# SCH.net
KiCad netlist of a schematic drawn in EasyEDA
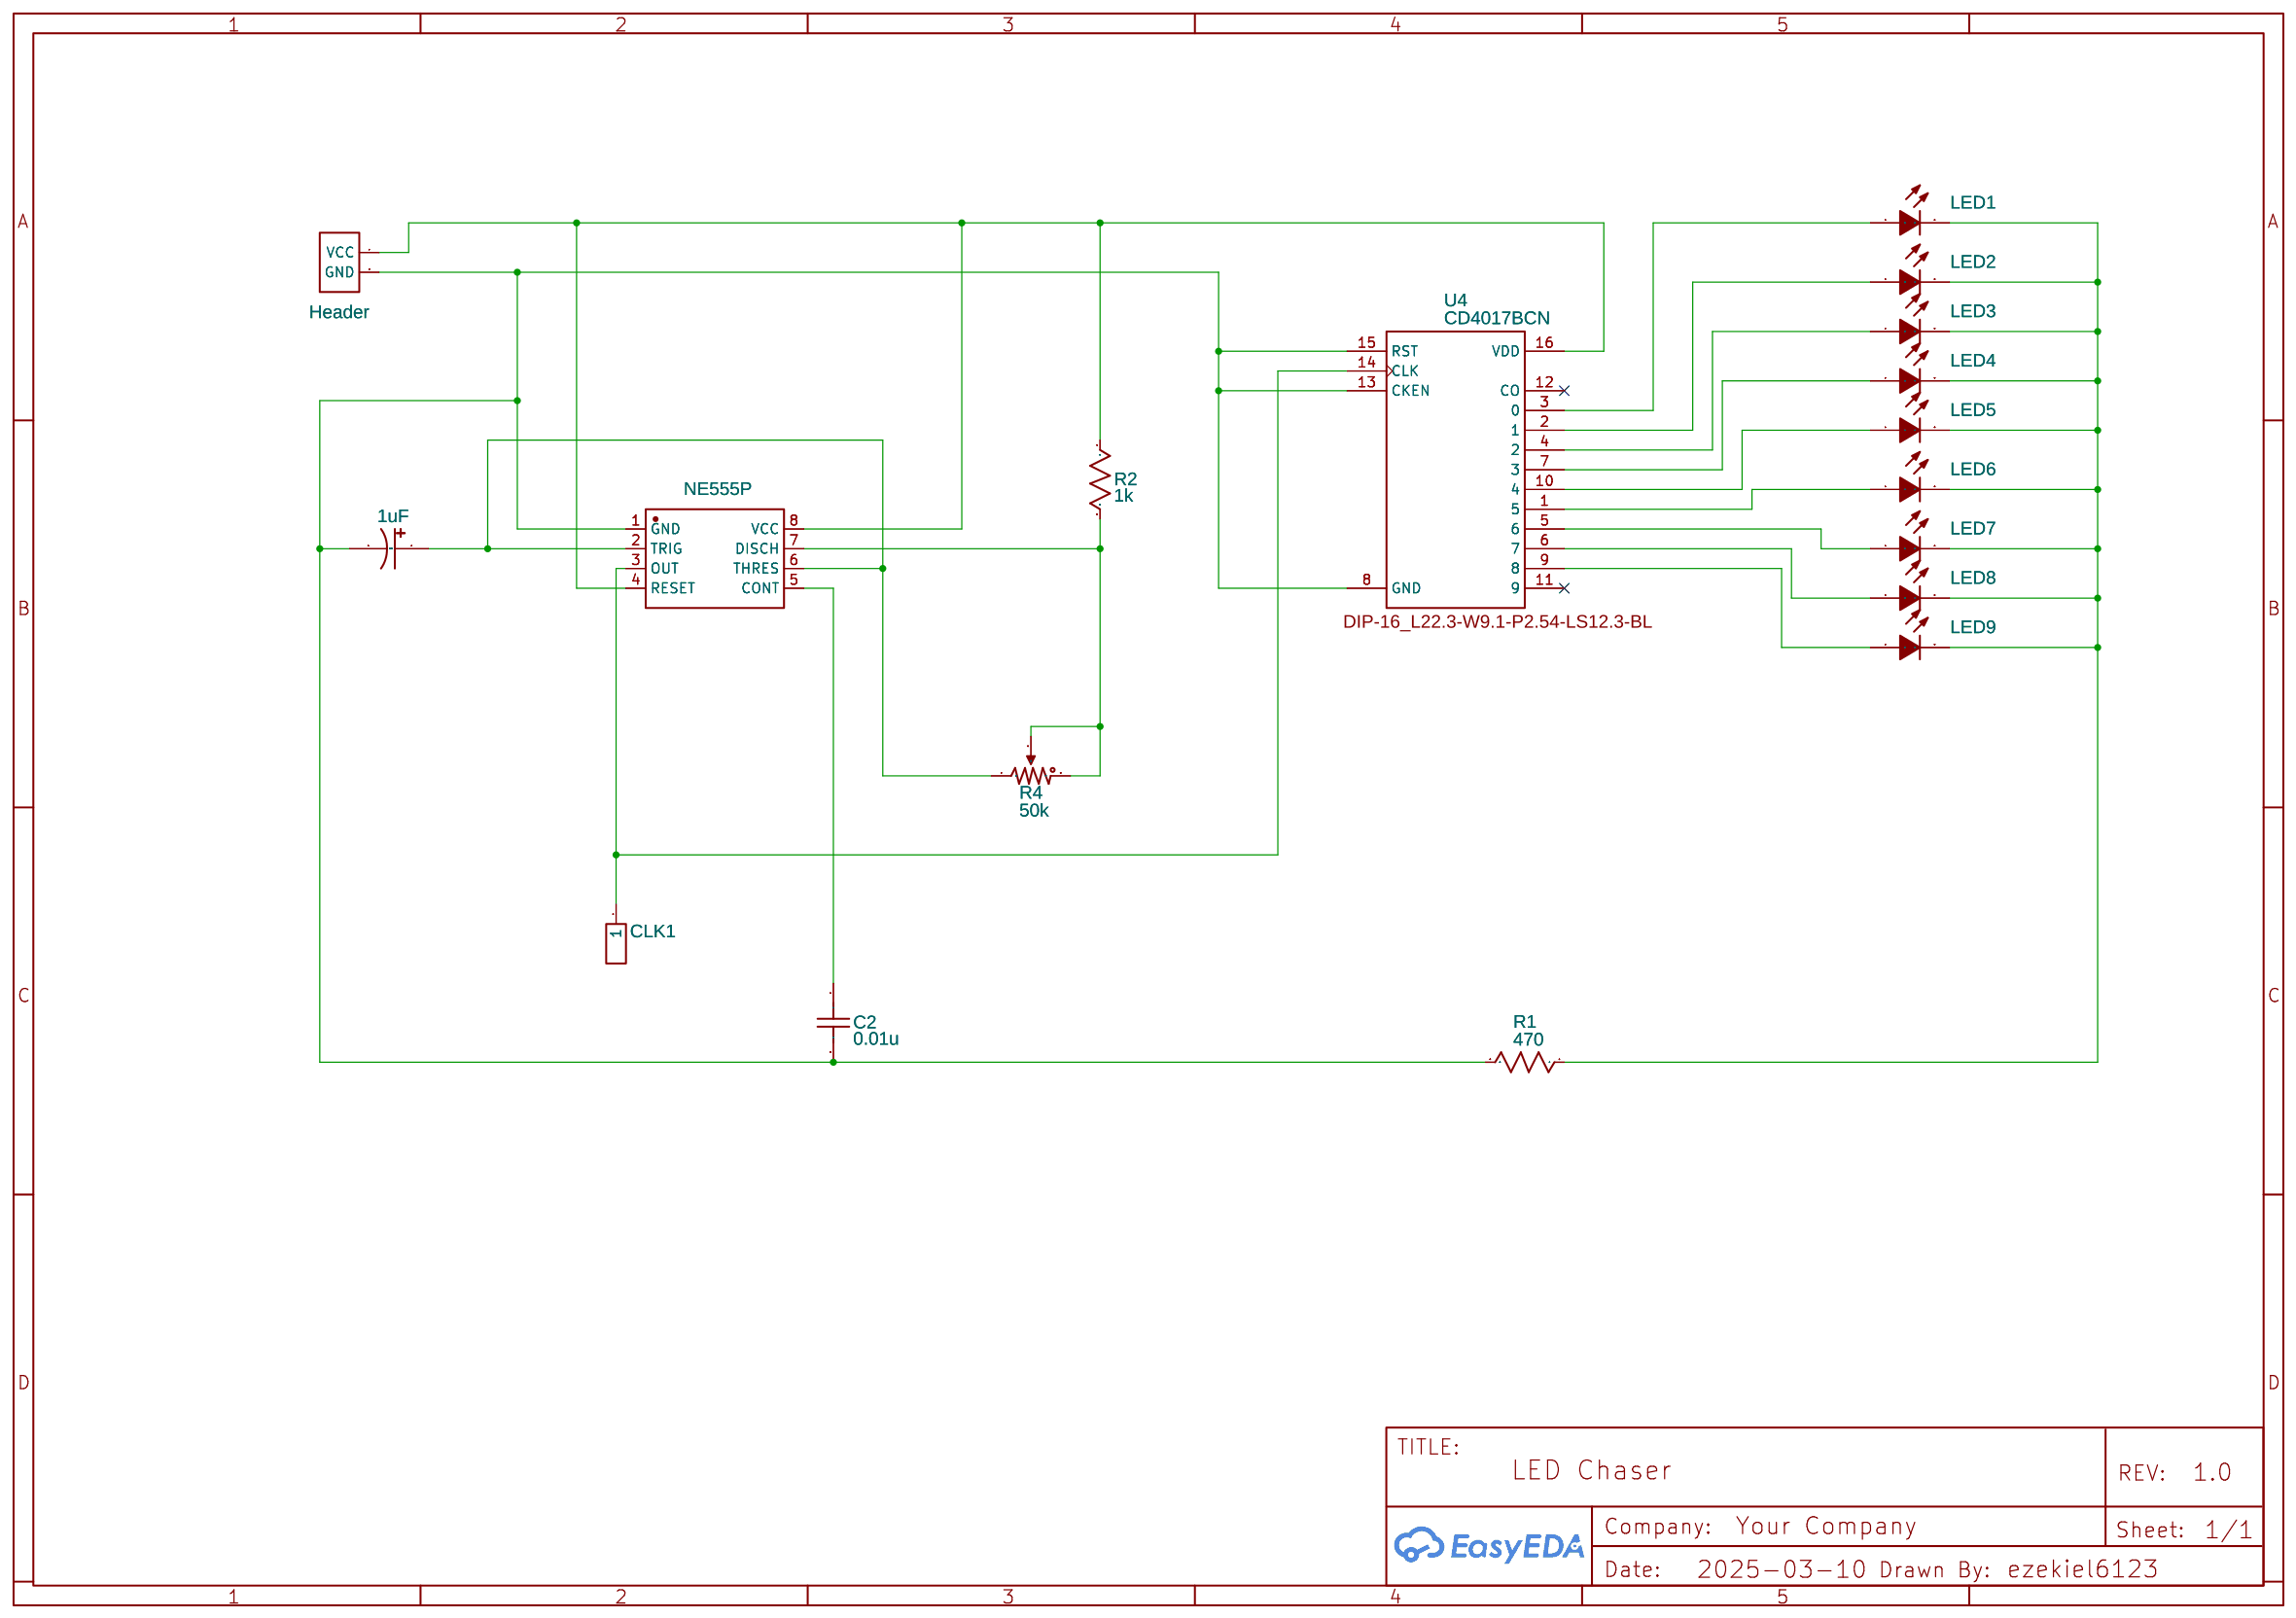
[diagram p0: schematic sheet]

(export (version "E")
  (design (tool "Eeschema 10.0.6"))
  (components
    (comp (ref "C1")
      (value "1uF")
      (fields (field (name "Manufacturer Part") "UVZ1H010MDD") (field (name "Manufacturer") "Nichicon(尼吉康)"))
      (libsource (lib "") (part "UVZ1H010MDD"))
    )
    (comp (ref "C2") (value "0.01u") (libsource (lib "") (part "C_0603_US")))
    (comp (ref "CLK1")
      (value "C81276")
      (fields
        (field (name "Manufacturer Part") "2.54-1*1P针")
        (field (name "Manufacturer") "BOOMELE(Boom Precision Elec)")
      )
      (libsource (lib "") (part "Header-Male-2.54_1x1"))
    )
    (comp (ref "H1") (value "Header") (libsource (lib "") (part "HEADER-FEMALE-2.54_1X2")))
    (comp (ref "LED1") (value "LED_5MM") (libsource (lib "") (part "LED_5MM")))
    (comp (ref "LED2") (value "LED_5MM") (libsource (lib "") (part "LED_5MM")))
    (comp (ref "LED3") (value "LED_5MM") (libsource (lib "") (part "LED_5MM")))
    (comp (ref "LED4") (value "LED_5MM") (libsource (lib "") (part "LED_5MM")))
    (comp (ref "LED5") (value "LED_5MM") (libsource (lib "") (part "LED_5MM")))
    (comp (ref "LED6") (value "LED_5MM") (libsource (lib "") (part "LED_5MM")))
    (comp (ref "LED7") (value "LED_5MM") (libsource (lib "") (part "LED_5MM")))
    (comp (ref "LED8") (value "LED_5MM") (libsource (lib "") (part "LED_5MM")))
    (comp (ref "LED9") (value "LED_5MM") (libsource (lib "") (part "LED_5MM")))
    (comp (ref "R1")
      (value "470")
      (fields (field (name "Manufacturer Part") "?"))
      (libsource (lib "") (part "Resistor"))
    )
    (comp (ref "R2")
      (value "1k")
      (fields (field (name "Manufacturer Part") "?"))
      (libsource (lib "") (part "Resistor_1"))
    )
    (comp (ref "R4")
      (value "50k")
      (fields (field (name "Manufacturer Part") "?"))
      (libsource (lib "") (part "Potentiometer"))
    )
    (comp (ref "U2")
      (value "NE555P")
      (fields (field (name "Manufacturer") "TI(德州仪器)"))
      (libsource (lib "") (part "NE555P"))
    )
    (comp (ref "U4") (value "CD4017BCN") (libsource (lib "") (part "CD4017BCN")))
  )
  (nets
    (net (code "1") (name "Net-(H1-GND)") (class "Default")
      (node (ref "C1") (pin "2") (pinfunction "2_2") (pintype "unspecified"))
      (node (ref "C2") (pin "2") (pinfunction "2_2") (pintype "unspecified"))
      (node (ref "H1") (pin "2") (pinfunction "GND_2") (pintype "unspecified"))
      (node (ref "R1") (pin "2") (pinfunction "2_2") (pintype "unspecified"))
      (node (ref "U2") (pin "1") (pinfunction "GND_1") (pintype "unspecified"))
      (node (ref "U4") (pin "13") (pinfunction "CKEN_13") (pintype "unspecified"))
      (node (ref "U4") (pin "15") (pinfunction "RST_15") (pintype "unspecified"))
      (node (ref "U4") (pin "8") (pinfunction "GND_8") (pintype "passive"))
    )
    (net (code "2") (name "Net-(H1-VCC)") (class "Default")
      (node (ref "H1") (pin "1") (pinfunction "VCC_1") (pintype "unspecified"))
      (node (ref "R2") (pin "1") (pinfunction "1_1") (pintype "unspecified"))
      (node (ref "U2") (pin "4") (pinfunction "RESET_4") (pintype "unspecified"))
      (node (ref "U2") (pin "8") (pinfunction "VCC_8") (pintype "unspecified"))
      (node (ref "U4") (pin "16") (pinfunction "VDD_16") (pintype "passive"))
    )
    (net (code "3") (name "Net-(LED1-A)") (class "Default")
      (node (ref "LED1") (pin "1") (pinfunction "A_1") (pintype "input"))
      (node (ref "U4") (pin "3") (pinfunction "0_3") (pintype "output"))
    )
    (net (code "4") (name "Net-(LED1-K)") (class "Default")
      (node (ref "LED1") (pin "2") (pinfunction "K_2") (pintype "input"))
      (node (ref "LED2") (pin "2") (pinfunction "K_2") (pintype "input"))
      (node (ref "LED3") (pin "2") (pinfunction "K_2") (pintype "input"))
      (node (ref "LED4") (pin "2") (pinfunction "K_2") (pintype "input"))
      (node (ref "LED5") (pin "2") (pinfunction "K_2") (pintype "input"))
      (node (ref "LED6") (pin "2") (pinfunction "K_2") (pintype "input"))
      (node (ref "LED7") (pin "2") (pinfunction "K_2") (pintype "input"))
      (node (ref "LED8") (pin "2") (pinfunction "K_2") (pintype "input"))
      (node (ref "LED9") (pin "2") (pinfunction "K_2") (pintype "input"))
      (node (ref "R1") (pin "1") (pinfunction "1_1") (pintype "unspecified"))
    )
    (net (code "5") (name "Net-(LED2-A)") (class "Default")
      (node (ref "LED2") (pin "1") (pinfunction "A_1") (pintype "input"))
      (node (ref "U4") (pin "2") (pinfunction "1_2") (pintype "output"))
    )
    (net (code "6") (name "Net-(LED3-A)") (class "Default")
      (node (ref "LED3") (pin "1") (pinfunction "A_1") (pintype "input"))
      (node (ref "U4") (pin "4") (pinfunction "2_4") (pintype "output"))
    )
    (net (code "7") (name "Net-(LED4-A)") (class "Default")
      (node (ref "LED4") (pin "1") (pinfunction "A_1") (pintype "input"))
      (node (ref "U4") (pin "7") (pinfunction "3_7") (pintype "output"))
    )
    (net (code "8") (name "Net-(LED5-A)") (class "Default")
      (node (ref "LED5") (pin "1") (pinfunction "A_1") (pintype "input"))
      (node (ref "U4") (pin "10") (pinfunction "4_10") (pintype "output"))
    )
    (net (code "9") (name "Net-(LED6-A)") (class "Default")
      (node (ref "LED6") (pin "1") (pinfunction "A_1") (pintype "input"))
      (node (ref "U4") (pin "1") (pinfunction "5_1") (pintype "output"))
    )
    (net (code "10") (name "Net-(LED7-A)") (class "Default")
      (node (ref "LED7") (pin "1") (pinfunction "A_1") (pintype "input"))
      (node (ref "U4") (pin "5") (pinfunction "6_5") (pintype "output"))
    )
    (net (code "11") (name "Net-(LED8-A)") (class "Default")
      (node (ref "LED8") (pin "1") (pinfunction "A_1") (pintype "input"))
      (node (ref "U4") (pin "6") (pinfunction "7_6") (pintype "output"))
    )
    (net (code "12") (name "Net-(LED9-A)") (class "Default")
      (node (ref "LED9") (pin "1") (pinfunction "A_1") (pintype "input"))
      (node (ref "U4") (pin "9") (pinfunction "8_9") (pintype "output"))
    )
    (net (code "13") (name "Net-(R4-2)") (class "Default")
      (node (ref "R2") (pin "2") (pinfunction "2_2") (pintype "unspecified"))
      (node (ref "R4") (pin "2") (pinfunction "3_2") (pintype "unspecified"))
      (node (ref "R4") (pin "3") (pinfunction "2_3") (pintype "unspecified"))
      (node (ref "U2") (pin "7") (pinfunction "DISCH_7") (pintype "unspecified"))
    )
    (net (code "14") (name "Net-(U2-CONT)") (class "Default")
      (node (ref "C2") (pin "1") (pinfunction "1_1") (pintype "unspecified"))
      (node (ref "U2") (pin "5") (pinfunction "CONT_5") (pintype "unspecified"))
    )
    (net (code "15") (name "Net-(U2-OUT)") (class "Default")
      (node (ref "CLK1") (pin "1") (pinfunction "1_1") (pintype "unspecified"))
      (node (ref "U2") (pin "3") (pinfunction "OUT_3") (pintype "unspecified"))
      (node (ref "U4") (pin "14") (pinfunction "CLK_14") (pintype "unspecified"))
    )
    (net (code "16") (name "Net-(U2-THRES)") (class "Default")
      (node (ref "C1") (pin "1") (pinfunction "1_1") (pintype "unspecified"))
      (node (ref "R4") (pin "1") (pinfunction "1_1") (pintype "unspecified"))
      (node (ref "U2") (pin "2") (pinfunction "TRIG_2") (pintype "unspecified"))
      (node (ref "U2") (pin "6") (pinfunction "THRES_6") (pintype "unspecified"))
    )
    (net (code "17") (name "unconnected-(U4-9-Pad11)") (class "Default")
      (node (ref "U4") (pin "11") (pinfunction "9_11") (pintype "output+no_connect"))
    )
    (net (code "18") (name "unconnected-(U4-CO-Pad12)") (class "Default")
      (node (ref "U4") (pin "12") (pinfunction "CO_12") (pintype "output+no_connect"))
    )
  )
)
